# Mako_DSP_Power_R1_2.net
KiCad netlist of a schematic drawn in Altium Designer
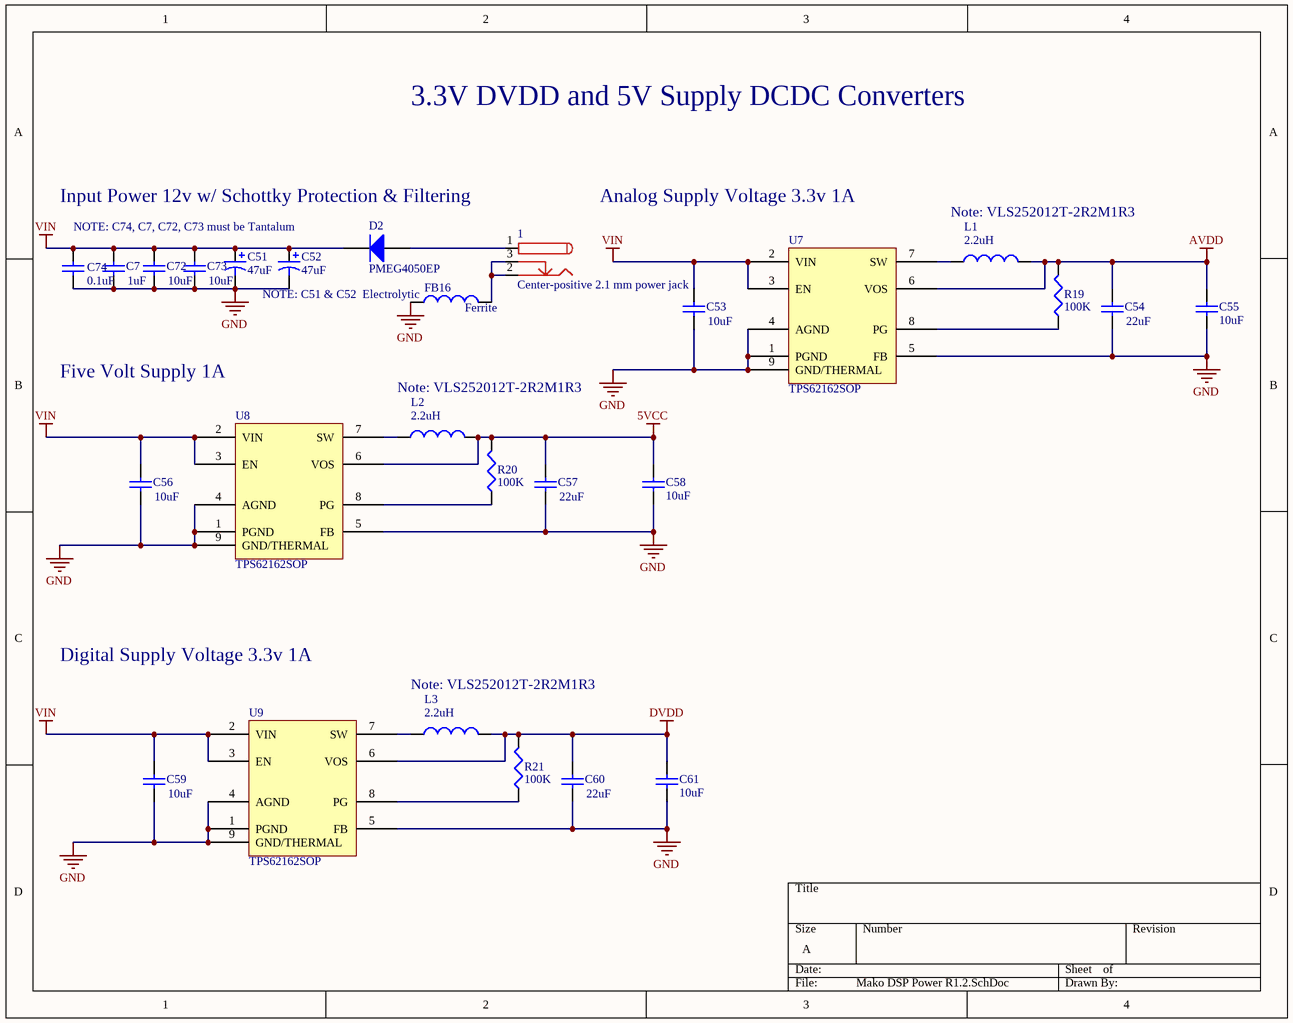
[diagram p0: Mako DSP Power R1.2.SchDoc]

(export (version "E")
  (design (tool "Eeschema 10.0.6"))
  (components
    (comp (ref "1")
      (value "Center-positive 2.1 mm power jack")
      (footprint "PJ-102AH")
      (description "Power jack")
      (fields (field (name "PUBLISHER") "Altium Limited"))
      (libsource (lib "Rascal") (part "PWR2.5"))
    )
    (comp (ref "C7")
      (value "1uF")
      (footprint "C1206")
      (description "Capacitor (Semiconductor SIM Model)")
      (fields (field (name "Comment") "Cap Semi") (field (name "PUBLISHER") "Altium Limited"))
      (libsource (lib "Miscellaneous Devices") (part "Cap Semi"))
    )
    (comp (ref "C51")
      (value "47uF")
      (footprint "CAPPR2.5-6.3x5")
      (description "Polarized Capacitor (Radial)")
      (fields (field (name "Comment") "Cap Pol1") (field (name "PUBLISHER") "Altium Limited"))
      (libsource (lib "Miscellaneous Devices") (part "Cap Pol1"))
    )
    (comp (ref "C52")
      (value "47uF")
      (footprint "CAPPR2.5-6.3x5")
      (description "Polarized Capacitor (Radial)")
      (fields (field (name "Comment") "Cap Pol1") (field (name "PUBLISHER") "Altium Limited"))
      (libsource (lib "Miscellaneous Devices") (part "Cap Pol1"))
    )
    (comp (ref "C53")
      (value "10uF")
      (footprint "C1206")
      (description "Capacitor (Semiconductor SIM Model)")
      (fields (field (name "Comment") "Cap Semi") (field (name "PUBLISHER") "Altium Limited"))
      (libsource (lib "Miscellaneous Devices") (part "Cap Semi"))
    )
    (comp (ref "C54")
      (value "22uF")
      (footprint "C1206")
      (description "Capacitor (Semiconductor SIM Model)")
      (fields (field (name "Comment") "Cap Semi") (field (name "PUBLISHER") "Altium Limited"))
      (libsource (lib "Miscellaneous Devices") (part "Cap Semi"))
    )
    (comp (ref "C55")
      (value "10uF")
      (footprint "Panasonic VS B")
      (description "Capacitor (Semiconductor SIM Model)")
      (fields (field (name "Comment") "Cap Semi") (field (name "PUBLISHER") "Altium Limited"))
      (libsource (lib "Miscellaneous Devices") (part "Cap Semi"))
    )
    (comp (ref "C56")
      (value "10uF")
      (footprint "C1206")
      (description "Capacitor (Semiconductor SIM Model)")
      (fields (field (name "Comment") "Cap Semi") (field (name "PUBLISHER") "Altium Limited"))
      (libsource (lib "Miscellaneous Devices") (part "Cap Semi"))
    )
    (comp (ref "C57")
      (value "22uF")
      (footprint "C1206")
      (description "Capacitor (Semiconductor SIM Model)")
      (fields (field (name "Comment") "Cap Semi") (field (name "PUBLISHER") "Altium Limited"))
      (libsource (lib "Miscellaneous Devices") (part "Cap Semi"))
    )
    (comp (ref "C58")
      (value "10uF")
      (footprint "Panasonic VS B")
      (description "Capacitor (Semiconductor SIM Model)")
      (fields (field (name "Comment") "Cap Semi") (field (name "PUBLISHER") "Altium Limited"))
      (libsource (lib "Miscellaneous Devices") (part "Cap Semi"))
    )
    (comp (ref "C59")
      (value "10uF")
      (footprint "C1206")
      (description "Capacitor (Semiconductor SIM Model)")
      (fields (field (name "Comment") "Cap Semi") (field (name "PUBLISHER") "Altium Limited"))
      (libsource (lib "Miscellaneous Devices") (part "Cap Semi"))
    )
    (comp (ref "C60")
      (value "22uF")
      (footprint "C1206")
      (description "Capacitor (Semiconductor SIM Model)")
      (fields (field (name "Comment") "Cap Semi") (field (name "PUBLISHER") "Altium Limited"))
      (libsource (lib "Miscellaneous Devices") (part "Cap Semi"))
    )
    (comp (ref "C61")
      (value "10uF")
      (footprint "Panasonic VS B")
      (description "Capacitor (Semiconductor SIM Model)")
      (fields (field (name "Comment") "Cap Semi") (field (name "PUBLISHER") "Altium Limited"))
      (libsource (lib "Miscellaneous Devices") (part "Cap Semi"))
    )
    (comp (ref "C72")
      (value "10uF")
      (footprint "C1206")
      (description "Capacitor (Semiconductor SIM Model)")
      (fields (field (name "Comment") "Cap Semi") (field (name "PUBLISHER") "Altium Limited"))
      (libsource (lib "Miscellaneous Devices") (part "Cap Semi"))
    )
    (comp (ref "C73")
      (value "10uF")
      (footprint "C1206")
      (description "Capacitor (Semiconductor SIM Model)")
      (fields (field (name "Comment") "Cap Semi") (field (name "PUBLISHER") "Altium Limited"))
      (libsource (lib "Miscellaneous Devices") (part "Cap Semi"))
    )
    (comp (ref "C74")
      (value "0.1uF")
      (footprint "C1206")
      (description "Capacitor (Semiconductor SIM Model)")
      (fields (field (name "Comment") "Cap Semi") (field (name "PUBLISHER") "Altium Limited"))
      (libsource (lib "Miscellaneous Devices") (part "Cap Semi"))
    )
    (comp (ref "D2")
      (value "PMEG4050EP")
      (footprint "PMEG4050EP")
      (description "Default Diode")
      (fields (field (name "PUBLISHER") "Altium Limited"))
      (libsource (lib "Miscellaneous Devices") (part "Diode"))
    )
    (comp (ref "FB16")
      (value "Ferrite")
      (footprint "SM 0805 - gap trimmed")
      (description "Inductor")
      (fields (field (name "PUBLISHER") "Altium Limited"))
      (libsource (lib "Miscellaneous Devices") (part "Inductor"))
    )
    (comp (ref "L1")
      (value "2.2uH")
      (footprint "VLS252012T-2R2M1R3")
      (description "Inductor")
      (fields (field (name "PUBLISHER") "Altium Limited"))
      (libsource (lib "Miscellaneous Devices") (part "Inductor"))
    )
    (comp (ref "L2")
      (value "2.2uH")
      (footprint "VLS252012T-2R2M1R3")
      (description "Inductor")
      (fields (field (name "PUBLISHER") "Altium Limited"))
      (libsource (lib "Miscellaneous Devices") (part "Inductor"))
    )
    (comp (ref "L3")
      (value "2.2uH")
      (footprint "VLS252012T-2R2M1R3")
      (description "Inductor")
      (fields (field (name "PUBLISHER") "Altium Limited"))
      (libsource (lib "Miscellaneous Devices") (part "Inductor"))
    )
    (comp (ref "R19")
      (value "100K")
      (footprint "RESC2012L")
      (description "Resistor")
      (fields (field (name "Comment") "Res3") (field (name "PUBLISHER") "Altium Limited"))
      (libsource (lib "Miscellaneous Devices") (part "Res3"))
    )
    (comp (ref "R20")
      (value "100K")
      (footprint "RESC2012L")
      (description "Resistor")
      (fields (field (name "Comment") "Res3") (field (name "PUBLISHER") "Altium Limited"))
      (libsource (lib "Miscellaneous Devices") (part "Res3"))
    )
    (comp (ref "R21")
      (value "100K")
      (footprint "RESC2012L")
      (description "Resistor")
      (fields (field (name "Comment") "Res3") (field (name "PUBLISHER") "Altium Limited"))
      (libsource (lib "Miscellaneous Devices") (part "Res3"))
    )
    (comp (ref "U7")
      (value "TPS62162SOP")
      (footprint "TPS62162SOP")
      (libsource (lib "Adams Altium Library") (part "TPS62162SOP"))
    )
    (comp (ref "U8")
      (value "TPS62162SOP")
      (footprint "TPS62162SOP")
      (libsource (lib "Adams Altium Library") (part "TPS62162SOP"))
    )
    (comp (ref "U9")
      (value "TPS62162SOP")
      (footprint "TPS62162SOP")
      (libsource (lib "Adams Altium Library") (part "TPS62162SOP"))
    )
  )
  (nets
    (net (code "1") (name "5VCC") (class "Default")
      (node (ref "C57") (pin "2") (pinfunction "2_2") (pintype "passive"))
      (node (ref "C58") (pin "1") (pinfunction "1_1") (pintype "passive"))
      (node (ref "L2") (pin "2") (pinfunction "2_2") (pintype "passive"))
      (node (ref "R20") (pin "2") (pinfunction "2_2") (pintype "passive"))
      (node (ref "U8") (pin "6") (pinfunction "VOS_6") (pintype "passive"))
    )
    (net (code "2") (name "AVDD") (class "Default")
      (node (ref "C54") (pin "2") (pinfunction "2_2") (pintype "passive"))
      (node (ref "C55") (pin "1") (pinfunction "1_1") (pintype "passive"))
      (node (ref "L1") (pin "2") (pinfunction "2_2") (pintype "passive"))
      (node (ref "R19") (pin "2") (pinfunction "2_2") (pintype "passive"))
      (node (ref "U7") (pin "6") (pinfunction "VOS_6") (pintype "passive"))
    )
    (net (code "3") (name "DVDD") (class "Default")
      (node (ref "C60") (pin "2") (pinfunction "2_2") (pintype "passive"))
      (node (ref "C61") (pin "1") (pinfunction "1_1") (pintype "passive"))
      (node (ref "L3") (pin "2") (pinfunction "2_2") (pintype "passive"))
      (node (ref "R21") (pin "2") (pinfunction "2_2") (pintype "passive"))
      (node (ref "U9") (pin "6") (pinfunction "VOS_6") (pintype "passive"))
    )
    (net (code "4") (name "GND") (class "Default")
      (node (ref "C51") (pin "2") (pinfunction "2_2") (pintype "passive"))
      (node (ref "C52") (pin "2") (pinfunction "2_2") (pintype "passive"))
      (node (ref "C53") (pin "1") (pinfunction "1_1") (pintype "passive"))
      (node (ref "C54") (pin "1") (pinfunction "1_1") (pintype "passive"))
      (node (ref "C55") (pin "2") (pinfunction "2_2") (pintype "passive"))
      (node (ref "C56") (pin "1") (pinfunction "1_1") (pintype "passive"))
      (node (ref "C57") (pin "1") (pinfunction "1_1") (pintype "passive"))
      (node (ref "C58") (pin "2") (pinfunction "2_2") (pintype "passive"))
      (node (ref "C59") (pin "1") (pinfunction "1_1") (pintype "passive"))
      (node (ref "C60") (pin "1") (pinfunction "1_1") (pintype "passive"))
      (node (ref "C61") (pin "2") (pinfunction "2_2") (pintype "passive"))
      (node (ref "C7") (pin "1") (pinfunction "1_1") (pintype "passive"))
      (node (ref "C72") (pin "1") (pinfunction "1_1") (pintype "passive"))
      (node (ref "C73") (pin "1") (pinfunction "1_1") (pintype "passive"))
      (node (ref "C74") (pin "1") (pinfunction "1_1") (pintype "passive"))
      (node (ref "FB16") (pin "1") (pinfunction "1_1") (pintype "passive"))
      (node (ref "U7") (pin "1") (pinfunction "PGND_1") (pintype "passive"))
      (node (ref "U7") (pin "4") (pinfunction "AGND_4") (pintype "passive"))
      (node (ref "U7") (pin "5") (pinfunction "FB_5") (pintype "passive"))
      (node (ref "U7") (pin "9") (pinfunction "GND/THERMAL_9") (pintype "passive"))
      (node (ref "U8") (pin "1") (pinfunction "PGND_1") (pintype "passive"))
      (node (ref "U8") (pin "4") (pinfunction "AGND_4") (pintype "passive"))
      (node (ref "U8") (pin "5") (pinfunction "FB_5") (pintype "passive"))
      (node (ref "U8") (pin "9") (pinfunction "GND/THERMAL_9") (pintype "passive"))
      (node (ref "U9") (pin "1") (pinfunction "PGND_1") (pintype "passive"))
      (node (ref "U9") (pin "4") (pinfunction "AGND_4") (pintype "passive"))
      (node (ref "U9") (pin "5") (pinfunction "FB_5") (pintype "passive"))
      (node (ref "U9") (pin "9") (pinfunction "GND/THERMAL_9") (pintype "passive"))
    )
    (net (code "5") (name "Net-(1-Pad2)") (class "Default")
      (node (ref "1") (pin "2") (pinfunction "2_2") (pintype "power_in"))
      (node (ref "1") (pin "3") (pinfunction "3_3") (pintype "power_in"))
      (node (ref "FB16") (pin "2") (pinfunction "2_2") (pintype "passive"))
    )
    (net (code "6") (name "Net-(D2-K)") (class "Default")
      (node (ref "1") (pin "1") (pinfunction "1_1") (pintype "power_in"))
      (node (ref "D2") (pin "2") (pinfunction "K_2") (pintype "passive"))
    )
    (net (code "7") (name "Net-(U7-PG)") (class "Default")
      (node (ref "R19") (pin "1") (pinfunction "1_1") (pintype "passive"))
      (node (ref "U7") (pin "8") (pinfunction "PG_8") (pintype "passive"))
    )
    (net (code "8") (name "Net-(U7-SW)") (class "Default")
      (node (ref "L1") (pin "1") (pinfunction "1_1") (pintype "passive"))
      (node (ref "U7") (pin "7") (pinfunction "SW_7") (pintype "passive"))
    )
    (net (code "9") (name "Net-(U8-PG)") (class "Default")
      (node (ref "R20") (pin "1") (pinfunction "1_1") (pintype "passive"))
      (node (ref "U8") (pin "8") (pinfunction "PG_8") (pintype "passive"))
    )
    (net (code "10") (name "Net-(U8-SW)") (class "Default")
      (node (ref "L2") (pin "1") (pinfunction "1_1") (pintype "passive"))
      (node (ref "U8") (pin "7") (pinfunction "SW_7") (pintype "passive"))
    )
    (net (code "11") (name "Net-(U9-PG)") (class "Default")
      (node (ref "R21") (pin "1") (pinfunction "1_1") (pintype "passive"))
      (node (ref "U9") (pin "8") (pinfunction "PG_8") (pintype "passive"))
    )
    (net (code "12") (name "Net-(U9-SW)") (class "Default")
      (node (ref "L3") (pin "1") (pinfunction "1_1") (pintype "passive"))
      (node (ref "U9") (pin "7") (pinfunction "SW_7") (pintype "passive"))
    )
    (net (code "13") (name "VIN") (class "Default")
      (node (ref "C51") (pin "1") (pinfunction "1_1") (pintype "passive"))
      (node (ref "C52") (pin "1") (pinfunction "1_1") (pintype "passive"))
      (node (ref "C53") (pin "2") (pinfunction "2_2") (pintype "passive"))
      (node (ref "C56") (pin "2") (pinfunction "2_2") (pintype "passive"))
      (node (ref "C59") (pin "2") (pinfunction "2_2") (pintype "passive"))
      (node (ref "C7") (pin "2") (pinfunction "2_2") (pintype "passive"))
      (node (ref "C72") (pin "2") (pinfunction "2_2") (pintype "passive"))
      (node (ref "C73") (pin "2") (pinfunction "2_2") (pintype "passive"))
      (node (ref "C74") (pin "2") (pinfunction "2_2") (pintype "passive"))
      (node (ref "D2") (pin "1") (pinfunction "A_1") (pintype "passive"))
      (node (ref "U7") (pin "2") (pinfunction "VIN_2") (pintype "passive"))
      (node (ref "U7") (pin "3") (pinfunction "EN_3") (pintype "passive"))
      (node (ref "U8") (pin "2") (pinfunction "VIN_2") (pintype "passive"))
      (node (ref "U8") (pin "3") (pinfunction "EN_3") (pintype "passive"))
      (node (ref "U9") (pin "2") (pinfunction "VIN_2") (pintype "passive"))
      (node (ref "U9") (pin "3") (pinfunction "EN_3") (pintype "passive"))
    )
  )
)
